# TM1638.net
KiCad netlist of a schematic drawn in Altium Designer
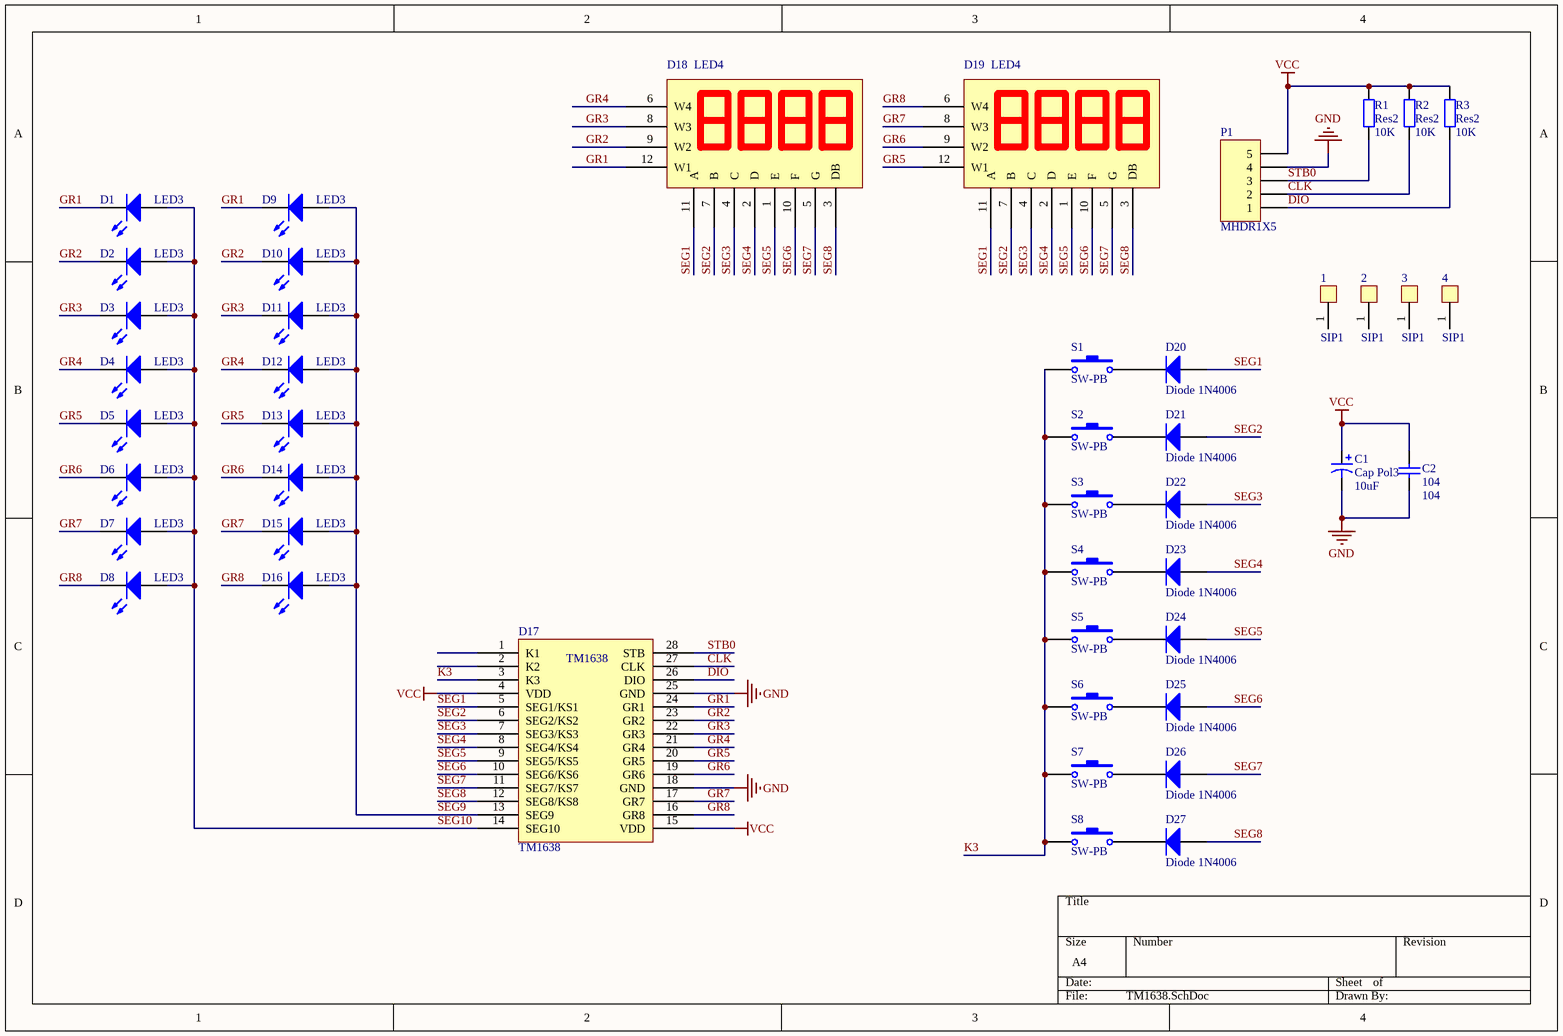
[diagram p0: TM1638.SchDoc]

(export (version "E")
  (design (tool "Eeschema 10.0.6"))
  (components
    (comp (ref "1")
      (value "SIP1")
      (footprint "hole")
      (description "Variable Resistor")
      (fields (field (name "PUBLISHER") "Altium Limited"))
      (libsource (lib "jointbar") (part "SIP1"))
    )
    (comp (ref "2")
      (value "SIP1")
      (footprint "hole")
      (description "Variable Resistor")
      (fields (field (name "PUBLISHER") "Altium Limited"))
      (libsource (lib "jointbar") (part "SIP1"))
    )
    (comp (ref "3")
      (value "SIP1")
      (footprint "hole")
      (description "Variable Resistor")
      (fields (field (name "PUBLISHER") "Altium Limited"))
      (libsource (lib "jointbar") (part "SIP1"))
    )
    (comp (ref "4")
      (value "SIP1")
      (footprint "hole")
      (description "Variable Resistor")
      (fields (field (name "PUBLISHER") "Altium Limited"))
      (libsource (lib "jointbar") (part "SIP1"))
    )
    (comp (ref "C1")
      (value "Cap Pol3")
      (footprint "0805")
      (description "Polarized Capacitor (Surface Mount)")
      (fields (field (name "ALTIUM_VALUE") "10uF") (field (name "PUBLISHER") "Altium Limited"))
      (libsource (lib "Miscellaneous Devices") (part "Cap Pol3"))
    )
    (comp (ref "C2")
      (value "104")
      (footprint "0805")
      (description "Capacitor (Semiconductor SIM Model)")
      (fields (field (name "ALTIUM_VALUE") "104") (field (name "PUBLISHER") "Altium Limited"))
      (libsource (lib "Miscellaneous Devices") (part "Cap Semi"))
    )
    (comp (ref "D1")
      (value "LED3")
      (footprint "LED0")
      (description "Typical BLUE SiC LED")
      (fields (field (name "PUBLISHER") "Altium Limited"))
      (libsource (lib "Miscellaneous Devices") (part "LED3"))
    )
    (comp (ref "D2")
      (value "LED3")
      (footprint "LED0")
      (description "Typical BLUE SiC LED")
      (fields (field (name "PUBLISHER") "Altium Limited"))
      (libsource (lib "Miscellaneous Devices") (part "LED3"))
    )
    (comp (ref "D3")
      (value "LED3")
      (footprint "LED0")
      (description "Typical BLUE SiC LED")
      (fields (field (name "PUBLISHER") "Altium Limited"))
      (libsource (lib "Miscellaneous Devices") (part "LED3"))
    )
    (comp (ref "D4")
      (value "LED3")
      (footprint "LED0")
      (description "Typical BLUE SiC LED")
      (fields (field (name "PUBLISHER") "Altium Limited"))
      (libsource (lib "Miscellaneous Devices") (part "LED3"))
    )
    (comp (ref "D5")
      (value "LED3")
      (footprint "LED0")
      (description "Typical BLUE SiC LED")
      (fields (field (name "PUBLISHER") "Altium Limited"))
      (libsource (lib "Miscellaneous Devices") (part "LED3"))
    )
    (comp (ref "D6")
      (value "LED3")
      (footprint "LED0")
      (description "Typical BLUE SiC LED")
      (fields (field (name "PUBLISHER") "Altium Limited"))
      (libsource (lib "Miscellaneous Devices") (part "LED3"))
    )
    (comp (ref "D7")
      (value "LED3")
      (footprint "LED0")
      (description "Typical BLUE SiC LED")
      (fields (field (name "PUBLISHER") "Altium Limited"))
      (libsource (lib "Miscellaneous Devices") (part "LED3"))
    )
    (comp (ref "D8")
      (value "LED3")
      (footprint "LED0")
      (description "Typical BLUE SiC LED")
      (fields (field (name "PUBLISHER") "Altium Limited"))
      (libsource (lib "Miscellaneous Devices") (part "LED3"))
    )
    (comp (ref "D9")
      (value "LED3")
      (footprint "LED0")
      (description "Typical BLUE SiC LED")
      (fields (field (name "PUBLISHER") "Altium Limited"))
      (libsource (lib "Miscellaneous Devices") (part "LED3"))
    )
    (comp (ref "D10")
      (value "LED3")
      (footprint "LED0")
      (description "Typical BLUE SiC LED")
      (fields (field (name "PUBLISHER") "Altium Limited"))
      (libsource (lib "Miscellaneous Devices") (part "LED3"))
    )
    (comp (ref "D11")
      (value "LED3")
      (footprint "LED0")
      (description "Typical BLUE SiC LED")
      (fields (field (name "PUBLISHER") "Altium Limited"))
      (libsource (lib "Miscellaneous Devices") (part "LED3"))
    )
    (comp (ref "D12")
      (value "LED3")
      (footprint "LED0")
      (description "Typical BLUE SiC LED")
      (fields (field (name "PUBLISHER") "Altium Limited"))
      (libsource (lib "Miscellaneous Devices") (part "LED3"))
    )
    (comp (ref "D13")
      (value "LED3")
      (footprint "LED0")
      (description "Typical BLUE SiC LED")
      (fields (field (name "PUBLISHER") "Altium Limited"))
      (libsource (lib "Miscellaneous Devices") (part "LED3"))
    )
    (comp (ref "D14")
      (value "LED3")
      (footprint "LED0")
      (description "Typical BLUE SiC LED")
      (fields (field (name "PUBLISHER") "Altium Limited"))
      (libsource (lib "Miscellaneous Devices") (part "LED3"))
    )
    (comp (ref "D15")
      (value "LED3")
      (footprint "LED0")
      (description "Typical BLUE SiC LED")
      (fields (field (name "PUBLISHER") "Altium Limited"))
      (libsource (lib "Miscellaneous Devices") (part "LED3"))
    )
    (comp (ref "D16")
      (value "LED3")
      (footprint "LED0")
      (description "Typical BLUE SiC LED")
      (fields (field (name "PUBLISHER") "Altium Limited"))
      (libsource (lib "Miscellaneous Devices") (part "LED3"))
    )
    (comp (ref "D17") (value "TM1638") (footprint "SOP28") (libsource (lib "AD620") (part "TM1638")))
    (comp (ref "D18") (value "LED4") (footprint "LED4") (libsource (lib "AD620") (part "LED_N4")))
    (comp (ref "D19") (value "LED4") (footprint "LED4") (libsource (lib "AD620") (part "LED_N4")))
    (comp (ref "D20")
      (value "Diode 1N4006")
      (footprint "1N4148")
      (description "1 Amp General Purpose Rectifier")
      (fields (field (name "PUBLISHER") "Altium Limited"))
      (libsource (lib "Miscellaneous Devices") (part "Diode 1N4006"))
    )
    (comp (ref "D21")
      (value "Diode 1N4006")
      (footprint "1N4148")
      (description "1 Amp General Purpose Rectifier")
      (fields (field (name "PUBLISHER") "Altium Limited"))
      (libsource (lib "Miscellaneous Devices") (part "Diode 1N4006"))
    )
    (comp (ref "D22")
      (value "Diode 1N4006")
      (footprint "1N4148")
      (description "1 Amp General Purpose Rectifier")
      (fields (field (name "PUBLISHER") "Altium Limited"))
      (libsource (lib "Miscellaneous Devices") (part "Diode 1N4006"))
    )
    (comp (ref "D23")
      (value "Diode 1N4006")
      (footprint "1N4148")
      (description "1 Amp General Purpose Rectifier")
      (fields (field (name "PUBLISHER") "Altium Limited"))
      (libsource (lib "Miscellaneous Devices") (part "Diode 1N4006"))
    )
    (comp (ref "D24")
      (value "Diode 1N4006")
      (footprint "1N4148")
      (description "1 Amp General Purpose Rectifier")
      (fields (field (name "PUBLISHER") "Altium Limited"))
      (libsource (lib "Miscellaneous Devices") (part "Diode 1N4006"))
    )
    (comp (ref "D25")
      (value "Diode 1N4006")
      (footprint "1N4148")
      (description "1 Amp General Purpose Rectifier")
      (fields (field (name "PUBLISHER") "Altium Limited"))
      (libsource (lib "Miscellaneous Devices") (part "Diode 1N4006"))
    )
    (comp (ref "D26")
      (value "Diode 1N4006")
      (footprint "1N4148")
      (description "1 Amp General Purpose Rectifier")
      (fields (field (name "PUBLISHER") "Altium Limited"))
      (libsource (lib "Miscellaneous Devices") (part "Diode 1N4006"))
    )
    (comp (ref "D27")
      (value "Diode 1N4006")
      (footprint "1N4148")
      (description "1 Amp General Purpose Rectifier")
      (fields (field (name "PUBLISHER") "Altium Limited"))
      (libsource (lib "Miscellaneous Devices") (part "Diode 1N4006"))
    )
    (comp (ref "P1")
      (value "MHDR1X5")
      (footprint "CON5")
      (description "Header, 5-Pin")
      (fields (field (name "PUBLISHER") "Altium Limited"))
      (libsource (lib "Miscellaneous Connectors") (part "MHDR1X5"))
    )
    (comp (ref "R1")
      (value "Res2")
      (footprint "0805")
      (description "Resistor")
      (fields (field (name "ALTIUM_VALUE") "10K") (field (name "PUBLISHER") "Altium Limited"))
      (libsource (lib "Miscellaneous Devices") (part "Res2"))
    )
    (comp (ref "R2")
      (value "Res2")
      (footprint "0805")
      (description "Resistor")
      (fields (field (name "ALTIUM_VALUE") "10K") (field (name "PUBLISHER") "Altium Limited"))
      (libsource (lib "Miscellaneous Devices") (part "Res2"))
    )
    (comp (ref "R3")
      (value "Res2")
      (footprint "0805")
      (description "Resistor")
      (fields (field (name "ALTIUM_VALUE") "10K") (field (name "PUBLISHER") "Altium Limited"))
      (libsource (lib "Miscellaneous Devices") (part "Res2"))
    )
    (comp (ref "S1")
      (value "SW-PB")
      (footprint "key")
      (description "Switch")
      (fields (field (name "PUBLISHER") "Altium Limited"))
      (libsource (lib "Miscellaneous Devices") (part "SW-PB"))
    )
    (comp (ref "S2")
      (value "SW-PB")
      (footprint "key")
      (description "Switch")
      (fields (field (name "PUBLISHER") "Altium Limited"))
      (libsource (lib "Miscellaneous Devices") (part "SW-PB"))
    )
    (comp (ref "S3")
      (value "SW-PB")
      (footprint "key")
      (description "Switch")
      (fields (field (name "PUBLISHER") "Altium Limited"))
      (libsource (lib "Miscellaneous Devices") (part "SW-PB"))
    )
    (comp (ref "S4")
      (value "SW-PB")
      (footprint "key")
      (description "Switch")
      (fields (field (name "PUBLISHER") "Altium Limited"))
      (libsource (lib "Miscellaneous Devices") (part "SW-PB"))
    )
    (comp (ref "S5")
      (value "SW-PB")
      (footprint "key")
      (description "Switch")
      (fields (field (name "PUBLISHER") "Altium Limited"))
      (libsource (lib "Miscellaneous Devices") (part "SW-PB"))
    )
    (comp (ref "S6")
      (value "SW-PB")
      (footprint "key")
      (description "Switch")
      (fields (field (name "PUBLISHER") "Altium Limited"))
      (libsource (lib "Miscellaneous Devices") (part "SW-PB"))
    )
    (comp (ref "S7")
      (value "SW-PB")
      (footprint "key")
      (description "Switch")
      (fields (field (name "PUBLISHER") "Altium Limited"))
      (libsource (lib "Miscellaneous Devices") (part "SW-PB"))
    )
    (comp (ref "S8")
      (value "SW-PB")
      (footprint "key")
      (description "Switch")
      (fields (field (name "PUBLISHER") "Altium Limited"))
      (libsource (lib "Miscellaneous Devices") (part "SW-PB"))
    )
  )
  (nets
    (net (code "1") (name "/CLK") (class "Default")
      (node (ref "D17") (pin "27") (pinfunction "CLK_27") (pintype "passive"))
      (node (ref "P1") (pin "2") (pinfunction "2_2") (pintype "passive"))
      (node (ref "R2") (pin "1") (pinfunction "1_1") (pintype "passive"))
    )
    (net (code "2") (name "/DIO") (class "Default")
      (node (ref "D17") (pin "26") (pinfunction "DIO_26") (pintype "passive"))
      (node (ref "P1") (pin "1") (pinfunction "1_1") (pintype "passive"))
      (node (ref "R3") (pin "1") (pinfunction "1_1") (pintype "passive"))
    )
    (net (code "3") (name "/GR1") (class "Default")
      (node (ref "D1") (pin "2") (pinfunction "K_2") (pintype "passive"))
      (node (ref "D17") (pin "24") (pinfunction "GR1_24") (pintype "passive"))
      (node (ref "D18") (pin "12") (pinfunction "W1_12") (pintype "passive"))
      (node (ref "D9") (pin "2") (pinfunction "K_2") (pintype "passive"))
    )
    (net (code "4") (name "/GR2") (class "Default")
      (node (ref "D10") (pin "2") (pinfunction "K_2") (pintype "passive"))
      (node (ref "D17") (pin "23") (pinfunction "GR2_23") (pintype "passive"))
      (node (ref "D18") (pin "9") (pinfunction "W2_9") (pintype "passive"))
      (node (ref "D2") (pin "2") (pinfunction "K_2") (pintype "passive"))
    )
    (net (code "5") (name "/GR3") (class "Default")
      (node (ref "D11") (pin "2") (pinfunction "K_2") (pintype "passive"))
      (node (ref "D17") (pin "22") (pinfunction "GR3_22") (pintype "passive"))
      (node (ref "D18") (pin "8") (pinfunction "W3_8") (pintype "passive"))
      (node (ref "D3") (pin "2") (pinfunction "K_2") (pintype "passive"))
    )
    (net (code "6") (name "/GR4") (class "Default")
      (node (ref "D12") (pin "2") (pinfunction "K_2") (pintype "passive"))
      (node (ref "D17") (pin "21") (pinfunction "GR4_21") (pintype "passive"))
      (node (ref "D18") (pin "6") (pinfunction "W4_6") (pintype "passive"))
      (node (ref "D4") (pin "2") (pinfunction "K_2") (pintype "passive"))
    )
    (net (code "7") (name "/GR5") (class "Default")
      (node (ref "D13") (pin "2") (pinfunction "K_2") (pintype "passive"))
      (node (ref "D17") (pin "20") (pinfunction "GR5_20") (pintype "passive"))
      (node (ref "D19") (pin "12") (pinfunction "W1_12") (pintype "passive"))
      (node (ref "D5") (pin "2") (pinfunction "K_2") (pintype "passive"))
    )
    (net (code "8") (name "/GR6") (class "Default")
      (node (ref "D14") (pin "2") (pinfunction "K_2") (pintype "passive"))
      (node (ref "D17") (pin "19") (pinfunction "GR6_19") (pintype "passive"))
      (node (ref "D19") (pin "9") (pinfunction "W2_9") (pintype "passive"))
      (node (ref "D6") (pin "2") (pinfunction "K_2") (pintype "passive"))
    )
    (net (code "9") (name "/GR7") (class "Default")
      (node (ref "D15") (pin "2") (pinfunction "K_2") (pintype "passive"))
      (node (ref "D17") (pin "17") (pinfunction "GR7_17") (pintype "passive"))
      (node (ref "D19") (pin "8") (pinfunction "W3_8") (pintype "passive"))
      (node (ref "D7") (pin "2") (pinfunction "K_2") (pintype "passive"))
    )
    (net (code "10") (name "/GR8") (class "Default")
      (node (ref "D16") (pin "2") (pinfunction "K_2") (pintype "passive"))
      (node (ref "D17") (pin "16") (pinfunction "GR8_16") (pintype "passive"))
      (node (ref "D19") (pin "6") (pinfunction "W4_6") (pintype "passive"))
      (node (ref "D8") (pin "2") (pinfunction "K_2") (pintype "passive"))
    )
    (net (code "11") (name "/K3") (class "Default")
      (node (ref "D17") (pin "3") (pinfunction "K3_3") (pintype "passive"))
      (node (ref "S1") (pin "1") (pinfunction "1_1") (pintype "passive"))
      (node (ref "S2") (pin "1") (pinfunction "1_1") (pintype "passive"))
      (node (ref "S3") (pin "1") (pinfunction "1_1") (pintype "passive"))
      (node (ref "S4") (pin "1") (pinfunction "1_1") (pintype "passive"))
      (node (ref "S5") (pin "1") (pinfunction "1_1") (pintype "passive"))
      (node (ref "S6") (pin "1") (pinfunction "1_1") (pintype "passive"))
      (node (ref "S7") (pin "1") (pinfunction "1_1") (pintype "passive"))
      (node (ref "S8") (pin "1") (pinfunction "1_1") (pintype "passive"))
    )
    (net (code "12") (name "/SEG1") (class "Default")
      (node (ref "D17") (pin "5") (pinfunction "SEG1/KS1_5") (pintype "passive"))
      (node (ref "D18") (pin "11") (pinfunction "A_11") (pintype "passive"))
      (node (ref "D19") (pin "11") (pinfunction "A_11") (pintype "passive"))
      (node (ref "D20") (pin "1") (pinfunction "A_1") (pintype "passive"))
    )
    (net (code "13") (name "/SEG2") (class "Default")
      (node (ref "D17") (pin "6") (pinfunction "SEG2/KS2_6") (pintype "passive"))
      (node (ref "D18") (pin "7") (pinfunction "B_7") (pintype "passive"))
      (node (ref "D19") (pin "7") (pinfunction "B_7") (pintype "passive"))
      (node (ref "D21") (pin "1") (pinfunction "A_1") (pintype "passive"))
    )
    (net (code "14") (name "/SEG3") (class "Default")
      (node (ref "D17") (pin "7") (pinfunction "SEG3/KS3_7") (pintype "passive"))
      (node (ref "D18") (pin "4") (pinfunction "C_4") (pintype "passive"))
      (node (ref "D19") (pin "4") (pinfunction "C_4") (pintype "passive"))
      (node (ref "D22") (pin "1") (pinfunction "A_1") (pintype "passive"))
    )
    (net (code "15") (name "/SEG4") (class "Default")
      (node (ref "D17") (pin "8") (pinfunction "SEG4/KS4_8") (pintype "passive"))
      (node (ref "D18") (pin "2") (pinfunction "D_2") (pintype "passive"))
      (node (ref "D19") (pin "2") (pinfunction "D_2") (pintype "passive"))
      (node (ref "D23") (pin "1") (pinfunction "A_1") (pintype "passive"))
    )
    (net (code "16") (name "/SEG5") (class "Default")
      (node (ref "D17") (pin "9") (pinfunction "SEG5/KS5_9") (pintype "passive"))
      (node (ref "D18") (pin "1") (pinfunction "E_1") (pintype "passive"))
      (node (ref "D19") (pin "1") (pinfunction "E_1") (pintype "passive"))
      (node (ref "D24") (pin "1") (pinfunction "A_1") (pintype "passive"))
    )
    (net (code "17") (name "/SEG6") (class "Default")
      (node (ref "D17") (pin "10") (pinfunction "SEG6/KS6_10") (pintype "passive"))
      (node (ref "D18") (pin "10") (pinfunction "F_10") (pintype "passive"))
      (node (ref "D19") (pin "10") (pinfunction "F_10") (pintype "passive"))
      (node (ref "D25") (pin "1") (pinfunction "A_1") (pintype "passive"))
    )
    (net (code "18") (name "/SEG7") (class "Default")
      (node (ref "D17") (pin "11") (pinfunction "SEG7/KS7_11") (pintype "passive"))
      (node (ref "D18") (pin "5") (pinfunction "G_5") (pintype "passive"))
      (node (ref "D19") (pin "5") (pinfunction "G_5") (pintype "passive"))
      (node (ref "D26") (pin "1") (pinfunction "A_1") (pintype "passive"))
    )
    (net (code "19") (name "/SEG8") (class "Default")
      (node (ref "D17") (pin "12") (pinfunction "SEG8/KS8_12") (pintype "passive"))
      (node (ref "D18") (pin "3") (pinfunction "DB_3") (pintype "passive"))
      (node (ref "D19") (pin "3") (pinfunction "DB_3") (pintype "passive"))
      (node (ref "D27") (pin "1") (pinfunction "A_1") (pintype "passive"))
    )
    (net (code "20") (name "/SEG9") (class "Default")
      (node (ref "D10") (pin "1") (pinfunction "A_1") (pintype "passive"))
      (node (ref "D11") (pin "1") (pinfunction "A_1") (pintype "passive"))
      (node (ref "D12") (pin "1") (pinfunction "A_1") (pintype "passive"))
      (node (ref "D13") (pin "1") (pinfunction "A_1") (pintype "passive"))
      (node (ref "D14") (pin "1") (pinfunction "A_1") (pintype "passive"))
      (node (ref "D15") (pin "1") (pinfunction "A_1") (pintype "passive"))
      (node (ref "D16") (pin "1") (pinfunction "A_1") (pintype "passive"))
      (node (ref "D17") (pin "13") (pinfunction "SEG9_13") (pintype "passive"))
      (node (ref "D9") (pin "1") (pinfunction "A_1") (pintype "passive"))
    )
    (net (code "21") (name "/SEG10") (class "Default")
      (node (ref "D1") (pin "1") (pinfunction "A_1") (pintype "passive"))
      (node (ref "D17") (pin "14") (pinfunction "SEG10_14") (pintype "passive"))
      (node (ref "D2") (pin "1") (pinfunction "A_1") (pintype "passive"))
      (node (ref "D3") (pin "1") (pinfunction "A_1") (pintype "passive"))
      (node (ref "D4") (pin "1") (pinfunction "A_1") (pintype "passive"))
      (node (ref "D5") (pin "1") (pinfunction "A_1") (pintype "passive"))
      (node (ref "D6") (pin "1") (pinfunction "A_1") (pintype "passive"))
      (node (ref "D7") (pin "1") (pinfunction "A_1") (pintype "passive"))
      (node (ref "D8") (pin "1") (pinfunction "A_1") (pintype "passive"))
    )
    (net (code "22") (name "/STB0") (class "Default")
      (node (ref "D17") (pin "28") (pinfunction "STB_28") (pintype "passive"))
      (node (ref "P1") (pin "3") (pinfunction "3_3") (pintype "passive"))
      (node (ref "R1") (pin "1") (pinfunction "1_1") (pintype "passive"))
    )
    (net (code "23") (name "GND") (class "Default")
      (node (ref "C1") (pin "2") (pinfunction "2_2") (pintype "passive"))
      (node (ref "C2") (pin "1") (pinfunction "1_1") (pintype "passive"))
      (node (ref "D17") (pin "18") (pinfunction "GND_18") (pintype "passive"))
      (node (ref "D17") (pin "25") (pinfunction "GND_25") (pintype "passive"))
      (node (ref "P1") (pin "4") (pinfunction "4_4") (pintype "passive"))
    )
    (net (code "24") (name "Net-(D20-K)") (class "Default")
      (node (ref "D20") (pin "2") (pinfunction "K_2") (pintype "passive"))
      (node (ref "S1") (pin "2") (pinfunction "2_2") (pintype "passive"))
    )
    (net (code "25") (name "Net-(D21-K)") (class "Default")
      (node (ref "D21") (pin "2") (pinfunction "K_2") (pintype "passive"))
      (node (ref "S2") (pin "2") (pinfunction "2_2") (pintype "passive"))
    )
    (net (code "26") (name "Net-(D22-K)") (class "Default")
      (node (ref "D22") (pin "2") (pinfunction "K_2") (pintype "passive"))
      (node (ref "S3") (pin "2") (pinfunction "2_2") (pintype "passive"))
    )
    (net (code "27") (name "Net-(D23-K)") (class "Default")
      (node (ref "D23") (pin "2") (pinfunction "K_2") (pintype "passive"))
      (node (ref "S4") (pin "2") (pinfunction "2_2") (pintype "passive"))
    )
    (net (code "28") (name "Net-(D24-K)") (class "Default")
      (node (ref "D24") (pin "2") (pinfunction "K_2") (pintype "passive"))
      (node (ref "S5") (pin "2") (pinfunction "2_2") (pintype "passive"))
    )
    (net (code "29") (name "Net-(D25-K)") (class "Default")
      (node (ref "D25") (pin "2") (pinfunction "K_2") (pintype "passive"))
      (node (ref "S6") (pin "2") (pinfunction "2_2") (pintype "passive"))
    )
    (net (code "30") (name "Net-(D26-K)") (class "Default")
      (node (ref "D26") (pin "2") (pinfunction "K_2") (pintype "passive"))
      (node (ref "S7") (pin "2") (pinfunction "2_2") (pintype "passive"))
    )
    (net (code "31") (name "Net-(D27-K)") (class "Default")
      (node (ref "D27") (pin "2") (pinfunction "K_2") (pintype "passive"))
      (node (ref "S8") (pin "2") (pinfunction "2_2") (pintype "passive"))
    )
    (net (code "32") (name "VCC") (class "Default")
      (node (ref "C1") (pin "1") (pinfunction "1_1") (pintype "passive"))
      (node (ref "C2") (pin "2") (pinfunction "2_2") (pintype "passive"))
      (node (ref "D17") (pin "15") (pinfunction "VDD_15") (pintype "passive"))
      (node (ref "D17") (pin "4") (pinfunction "VDD_4") (pintype "passive"))
      (node (ref "P1") (pin "5") (pinfunction "5_5") (pintype "passive"))
      (node (ref "R1") (pin "2") (pinfunction "2_2") (pintype "passive"))
      (node (ref "R2") (pin "2") (pinfunction "2_2") (pintype "passive"))
      (node (ref "R3") (pin "2") (pinfunction "2_2") (pintype "passive"))
    )
    (net (code "33") (name "unconnected-(1-Pad1)") (class "Default")
      (node (ref "1") (pin "1") (pinfunction "1_1") (pintype "passive"))
    )
    (net (code "34") (name "unconnected-(2-Pad1)") (class "Default")
      (node (ref "2") (pin "1") (pinfunction "1_1") (pintype "passive"))
    )
    (net (code "35") (name "unconnected-(3-Pad1)") (class "Default")
      (node (ref "3") (pin "1") (pinfunction "1_1") (pintype "passive"))
    )
    (net (code "36") (name "unconnected-(4-Pad1)") (class "Default")
      (node (ref "4") (pin "1") (pinfunction "1_1") (pintype "passive"))
    )
    (net (code "37") (name "unconnected-(D17-K1-Pad1)") (class "Default")
      (node (ref "D17") (pin "1") (pinfunction "K1_1") (pintype "passive"))
    )
    (net (code "38") (name "unconnected-(D17-K2-Pad2)") (class "Default")
      (node (ref "D17") (pin "2") (pinfunction "K2_2") (pintype "passive"))
    )
  )
)
